# energy.net
KiCad netlist of a schematic drawn in EAGLE
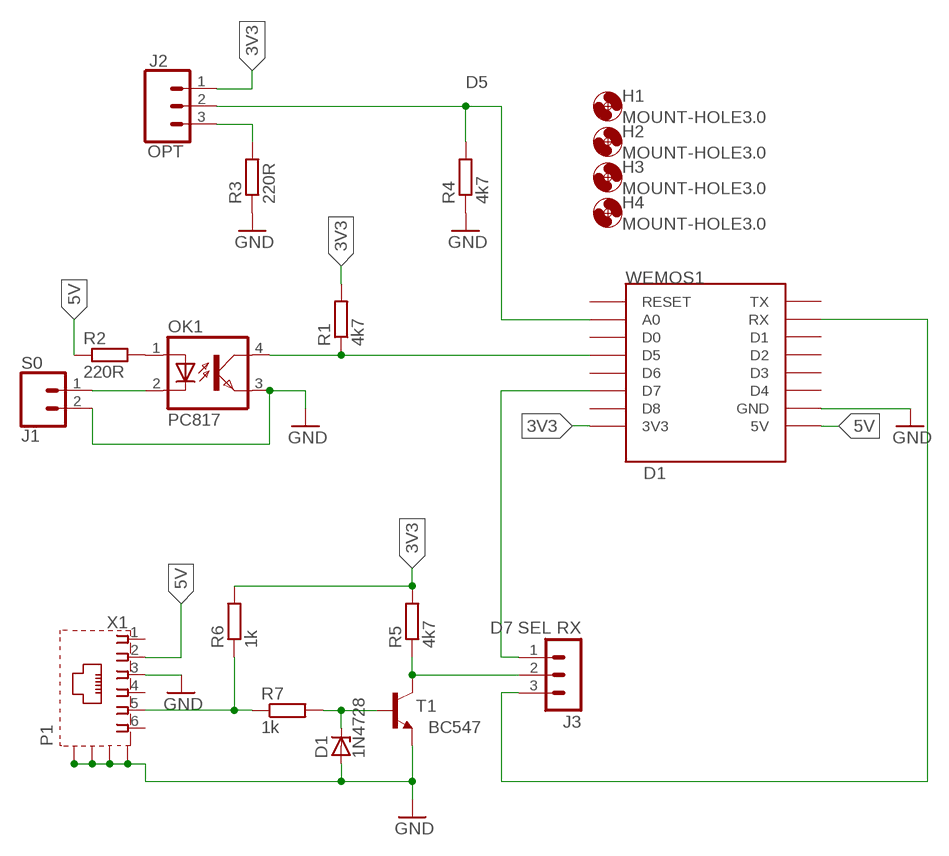
[diagram p0: schematic, sheet 1]

(export (version "E")
  (design (tool "Eeschema 10.0.6"))
  (components
    (comp (ref "D1")
      (value "1N4728")
      (footprint "eagle-import:DO41Z10")
      (libsource (lib "eagle-import") (part "1N4728"))
    )
    (comp (ref "H1")
      (value "MOUNT-HOLE3.0")
      (footprint "eagle-import:3,0")
      (libsource (lib "eagle-import") (part "MOUNT-HOLE3.0"))
    )
    (comp (ref "H2")
      (value "MOUNT-HOLE3.0")
      (footprint "eagle-import:3,0")
      (libsource (lib "eagle-import") (part "MOUNT-HOLE3.0"))
    )
    (comp (ref "H3")
      (value "MOUNT-HOLE3.0")
      (footprint "eagle-import:3,0")
      (libsource (lib "eagle-import") (part "MOUNT-HOLE3.0"))
    )
    (comp (ref "H4")
      (value "MOUNT-HOLE3.0")
      (footprint "eagle-import:3,0")
      (libsource (lib "eagle-import") (part "MOUNT-HOLE3.0"))
    )
    (comp (ref "J1")
      (value "S0")
      (footprint "eagle-import:SCREWTERMINAL-3.5MM-2")
      (libsource (lib "eagle-import") (part "CONN_023.5MM"))
    )
    (comp (ref "J2")
      (value "OPT")
      (footprint "eagle-import:SCREWTERMINAL-3.5MM-3")
      (libsource (lib "eagle-import") (part "CONN_03SCREW"))
    )
    (comp (ref "J3")
      (value "D7 SEL RX")
      (footprint "eagle-import:MA03-1")
      (libsource (lib "eagle-import") (part "MA03-1"))
    )
    (comp (ref "OK1")
      (value "PC817")
      (footprint "eagle-import:DIL04")
      (fields (field (name "MPN") "PC817X4J000F"))
      (libsource (lib "eagle-import") (part "PC817"))
    )
    (comp (ref "R1")
      (value "4k7")
      (footprint "eagle-import:0207_10")
      (libsource (lib "eagle-import") (part "R-EU_0207/10"))
    )
    (comp (ref "R2")
      (value "220R")
      (footprint "eagle-import:0207_10")
      (libsource (lib "eagle-import") (part "R-EU_0207/10"))
    )
    (comp (ref "R3")
      (value "220R")
      (footprint "eagle-import:0207_10")
      (libsource (lib "eagle-import") (part "R-EU_0207/10"))
    )
    (comp (ref "R4")
      (value "4k7")
      (footprint "eagle-import:0207_10")
      (libsource (lib "eagle-import") (part "R-EU_0207/10"))
    )
    (comp (ref "R5")
      (value "4k7")
      (footprint "eagle-import:0207_10")
      (libsource (lib "eagle-import") (part "R-EU_0207/10"))
    )
    (comp (ref "R6")
      (value "1k")
      (footprint "eagle-import:0207_10")
      (libsource (lib "eagle-import") (part "R-EU_0207/10"))
    )
    (comp (ref "R7")
      (value "1k")
      (footprint "eagle-import:0207_10")
      (libsource (lib "eagle-import") (part "R-EU_0207/10"))
    )
    (comp (ref "T1")
      (value "BC547")
      (footprint "eagle-import:TO92")
      (libsource (lib "eagle-import") (part "BC547"))
    )
    (comp (ref "WEMOS1")
      (value "D1")
      (footprint "eagle-import:WEMOS-D1-MINI")
      (libsource (lib "eagle-import") (part "WEMOS-D1-MINI"))
    )
    (comp (ref "X1")
      (value "P1")
      (footprint "eagle-import:RJ11-SHIELD2")
      (fields (field (name "MPN") "RJ11-6LCT2-B"))
      (libsource (lib "eagle-import") (part "RJ112-B-6LCT"))
    )
  )
  (nets
    (net (code "1") (name "/D5") (class "Default")
      (node (ref "OK1") (pin "4") (pinfunction "COL_4") (pintype "passive"))
      (node (ref "R1") (pin "1") (pinfunction "1_1") (pintype "passive"))
      (node (ref "WEMOS1") (pin "D5") (pinfunction "D5_D5") (pintype "bidirectional"))
    )
    (net (code "2") (name "3V3") (class "Default")
      (node (ref "J2") (pin "1") (pinfunction "1_1") (pintype "passive"))
      (node (ref "R1") (pin "2") (pinfunction "2_2") (pintype "passive"))
      (node (ref "R5") (pin "2") (pinfunction "2_2") (pintype "passive"))
      (node (ref "R6") (pin "2") (pinfunction "2_2") (pintype "passive"))
      (node (ref "WEMOS1") (pin "3V3") (pinfunction "3V3_3V3") (pintype "bidirectional"))
    )
    (net (code "3") (name "5V") (class "Default")
      (node (ref "R2") (pin "1") (pinfunction "1_1") (pintype "passive"))
      (node (ref "WEMOS1") (pin "5V") (pinfunction "5V_5V") (pintype "bidirectional"))
      (node (ref "X1") (pin "2") (pinfunction "2_2") (pintype "passive"))
    )
    (net (code "4") (name "GND") (class "Default")
      (node (ref "D1") (pin "A") (pinfunction "A_A") (pintype "passive"))
      (node (ref "J1") (pin "2") (pinfunction "2_2") (pintype "passive"))
      (node (ref "OK1") (pin "3") (pinfunction "EMIT_3") (pintype "passive"))
      (node (ref "R3") (pin "1") (pinfunction "1_1") (pintype "passive"))
      (node (ref "R4") (pin "1") (pinfunction "1_1") (pintype "passive"))
      (node (ref "T1") (pin "1") (pinfunction "E_1") (pintype "passive"))
      (node (ref "WEMOS1") (pin "GND") (pinfunction "GND_GND") (pintype "bidirectional"))
      (node (ref "X1") (pin "3") (pinfunction "3_3") (pintype "passive"))
      (node (ref "X1") (pin "S1") (pinfunction "S_S1") (pintype "passive"))
      (node (ref "X1") (pin "S2") (pinfunction "S_S2") (pintype "passive"))
      (node (ref "X1") (pin "S3") (pinfunction "S_S3") (pintype "passive"))
      (node (ref "X1") (pin "S4") (pinfunction "S_S4") (pintype "passive"))
    )
    (net (code "5") (name "Net-(J2-Pad2)") (class "Default")
      (node (ref "J2") (pin "2") (pinfunction "2_2") (pintype "passive"))
      (node (ref "R4") (pin "2") (pinfunction "2_2") (pintype "passive"))
      (node (ref "WEMOS1") (pin "A0") (pinfunction "A0_A0") (pintype "bidirectional"))
    )
    (net (code "6") (name "Net-(J2-Pad3)") (class "Default")
      (node (ref "J2") (pin "3") (pinfunction "3_3") (pintype "passive"))
      (node (ref "R3") (pin "2") (pinfunction "2_2") (pintype "passive"))
    )
    (net (code "7") (name "Net-(J3-Pad1)") (class "Default")
      (node (ref "J3") (pin "1") (pinfunction "1_1") (pintype "passive"))
      (node (ref "WEMOS1") (pin "D7") (pinfunction "D7_D7") (pintype "bidirectional"))
    )
    (net (code "8") (name "Net-(J3-Pad3)") (class "Default")
      (node (ref "J3") (pin "3") (pinfunction "3_3") (pintype "passive"))
      (node (ref "WEMOS1") (pin "RX") (pinfunction "RX_RX") (pintype "bidirectional"))
    )
    (net (code "9") (name "Net-(OK1-A)") (class "Default")
      (node (ref "OK1") (pin "1") (pinfunction "A_1") (pintype "passive"))
      (node (ref "R2") (pin "2") (pinfunction "2_2") (pintype "passive"))
    )
    (net (code "10") (name "Net-(OK1-C)") (class "Default")
      (node (ref "J1") (pin "1") (pinfunction "1_1") (pintype "passive"))
      (node (ref "OK1") (pin "2") (pinfunction "C_2") (pintype "passive"))
    )
    (net (code "11") (name "Net-(R6-Pad1)") (class "Default")
      (node (ref "R6") (pin "1") (pinfunction "1_1") (pintype "passive"))
      (node (ref "R7") (pin "1") (pinfunction "1_1") (pintype "passive"))
      (node (ref "X1") (pin "5") (pinfunction "5_5") (pintype "passive"))
    )
    (net (code "12") (name "Net-(T1-B)") (class "Default")
      (node (ref "D1") (pin "C") (pinfunction "C_C") (pintype "passive"))
      (node (ref "R7") (pin "2") (pinfunction "2_2") (pintype "passive"))
      (node (ref "T1") (pin "2") (pinfunction "B_2") (pintype "passive"))
    )
    (net (code "13") (name "Net-(T1-C)") (class "Default")
      (node (ref "J3") (pin "2") (pinfunction "2_2") (pintype "passive"))
      (node (ref "R5") (pin "1") (pinfunction "1_1") (pintype "passive"))
      (node (ref "T1") (pin "3") (pinfunction "C_3") (pintype "passive"))
    )
    (net (code "14") (name "unconnected-(WEMOS1-PadD0)") (class "Default")
      (node (ref "WEMOS1") (pin "D0") (pinfunction "D0_D0") (pintype "bidirectional"))
    )
    (net (code "15") (name "unconnected-(WEMOS1-PadD1)") (class "Default")
      (node (ref "WEMOS1") (pin "D1") (pinfunction "D1_D1") (pintype "bidirectional"))
    )
    (net (code "16") (name "unconnected-(WEMOS1-PadD2)") (class "Default")
      (node (ref "WEMOS1") (pin "D2") (pinfunction "D2_D2") (pintype "bidirectional"))
    )
    (net (code "17") (name "unconnected-(WEMOS1-PadD3)") (class "Default")
      (node (ref "WEMOS1") (pin "D3") (pinfunction "D3_D3") (pintype "bidirectional"))
    )
    (net (code "18") (name "unconnected-(WEMOS1-PadD4)") (class "Default")
      (node (ref "WEMOS1") (pin "D4") (pinfunction "D4_D4") (pintype "bidirectional"))
    )
    (net (code "19") (name "unconnected-(WEMOS1-PadD6)") (class "Default")
      (node (ref "WEMOS1") (pin "D6") (pinfunction "D6_D6") (pintype "bidirectional"))
    )
    (net (code "20") (name "unconnected-(WEMOS1-PadD8)") (class "Default")
      (node (ref "WEMOS1") (pin "D8") (pinfunction "D8_D8") (pintype "bidirectional"))
    )
    (net (code "21") (name "unconnected-(WEMOS1-PadRESET)") (class "Default")
      (node (ref "WEMOS1") (pin "RESET") (pinfunction "RESET_RESET") (pintype "bidirectional"))
    )
    (net (code "22") (name "unconnected-(WEMOS1-PadTX)") (class "Default")
      (node (ref "WEMOS1") (pin "TX") (pinfunction "TX_TX") (pintype "bidirectional"))
    )
    (net (code "23") (name "unconnected-(X1-Pad1)") (class "Default")
      (node (ref "X1") (pin "1") (pinfunction "1_1") (pintype "passive"))
    )
    (net (code "24") (name "unconnected-(X1-Pad4)") (class "Default")
      (node (ref "X1") (pin "4") (pinfunction "4_4") (pintype "passive"))
    )
    (net (code "25") (name "unconnected-(X1-Pad6)") (class "Default")
      (node (ref "X1") (pin "6") (pinfunction "6_6") (pintype "passive"))
    )
  )
)
